# RPiOperantBreakout.net
KiCad netlist of a schematic drawn in EAGLE
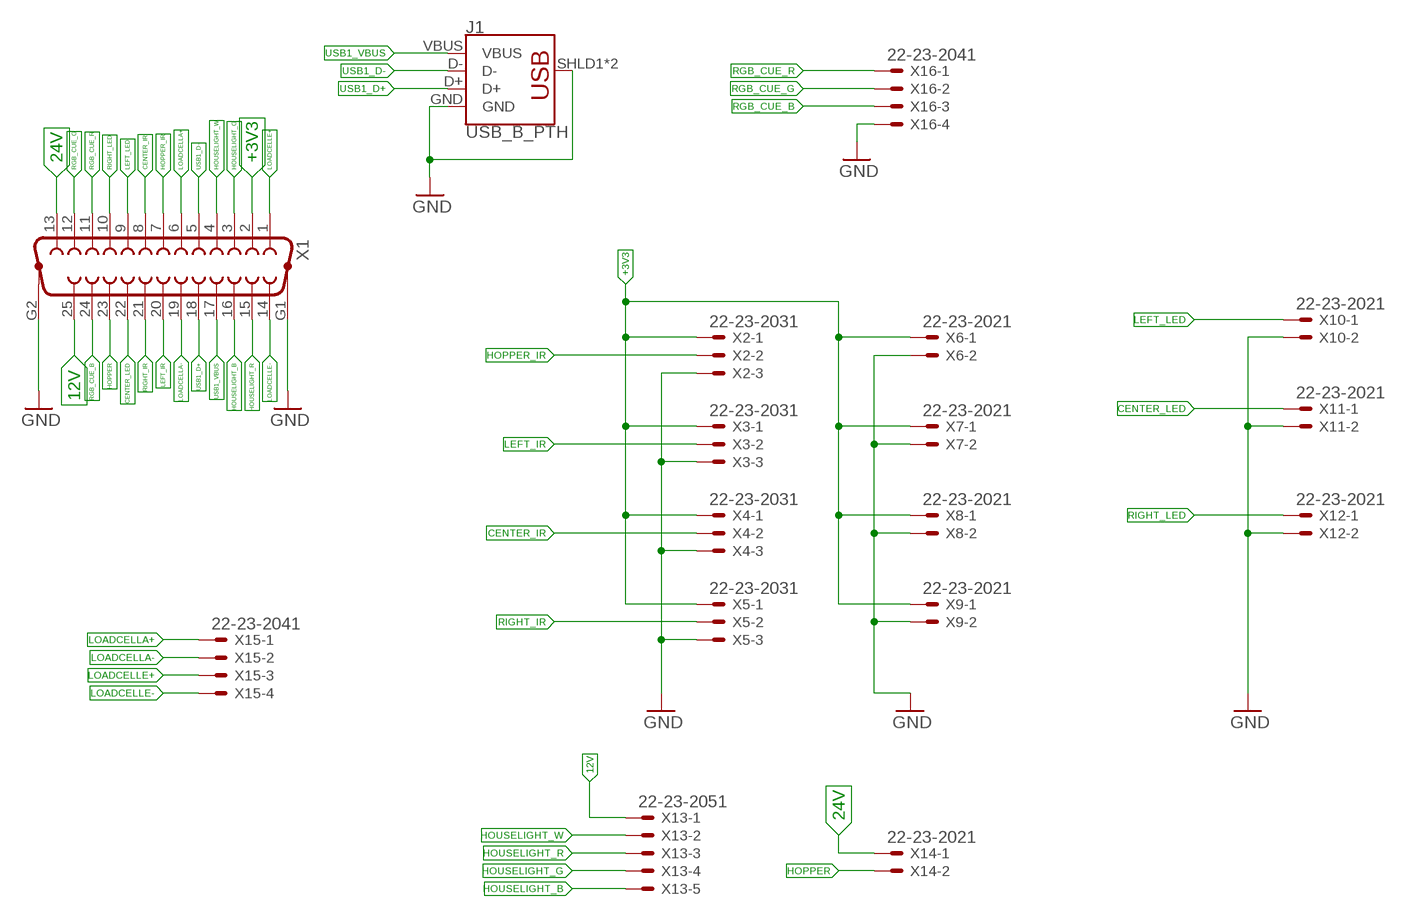
[diagram p0: schematic, sheet 1]

(export (version "E")
  (design (tool "Eeschema 10.0.6"))
  (components
    (comp (ref "J1")
      (value "USB_B_PTH")
      (footprint "eagle-import:USB-B-PTH")
      (libsource (lib "eagle-import") (part "USB_B_PTH"))
    )
    (comp (ref "X1")
      (value "F25HP")
      (footprint "eagle-import:F25HP")
      (libsource (lib "eagle-import") (part "F25HP"))
    )
    (comp (ref "X2")
      (value "22-23-2031")
      (footprint "eagle-import:22-23-2031")
      (fields (field (name "MF") "MOLEX"))
      (libsource (lib "eagle-import") (part "22-23-2031"))
    )
    (comp (ref "X3")
      (value "22-23-2031")
      (footprint "eagle-import:22-23-2031")
      (fields (field (name "MF") "MOLEX"))
      (libsource (lib "eagle-import") (part "22-23-2031"))
    )
    (comp (ref "X4")
      (value "22-23-2031")
      (footprint "eagle-import:22-23-2031")
      (fields (field (name "MF") "MOLEX"))
      (libsource (lib "eagle-import") (part "22-23-2031"))
    )
    (comp (ref "X5")
      (value "22-23-2031")
      (footprint "eagle-import:22-23-2031")
      (fields (field (name "MF") "MOLEX"))
      (libsource (lib "eagle-import") (part "22-23-2031"))
    )
    (comp (ref "X6")
      (value "22-23-2021")
      (footprint "eagle-import:22-23-2021")
      (fields (field (name "MF") "MOLEX"))
      (libsource (lib "eagle-import") (part "22-23-2021"))
    )
    (comp (ref "X7")
      (value "22-23-2021")
      (footprint "eagle-import:22-23-2021")
      (fields (field (name "MF") "MOLEX"))
      (libsource (lib "eagle-import") (part "22-23-2021"))
    )
    (comp (ref "X8")
      (value "22-23-2021")
      (footprint "eagle-import:22-23-2021")
      (fields (field (name "MF") "MOLEX"))
      (libsource (lib "eagle-import") (part "22-23-2021"))
    )
    (comp (ref "X9")
      (value "22-23-2021")
      (footprint "eagle-import:22-23-2021")
      (fields (field (name "MF") "MOLEX"))
      (libsource (lib "eagle-import") (part "22-23-2021"))
    )
    (comp (ref "X10")
      (value "22-23-2021")
      (footprint "eagle-import:22-23-2021")
      (fields (field (name "MF") "MOLEX"))
      (libsource (lib "eagle-import") (part "22-23-2021"))
    )
    (comp (ref "X11")
      (value "22-23-2021")
      (footprint "eagle-import:22-23-2021")
      (fields (field (name "MF") "MOLEX"))
      (libsource (lib "eagle-import") (part "22-23-2021"))
    )
    (comp (ref "X12")
      (value "22-23-2021")
      (footprint "eagle-import:22-23-2021")
      (fields (field (name "MF") "MOLEX"))
      (libsource (lib "eagle-import") (part "22-23-2021"))
    )
    (comp (ref "X13")
      (value "22-23-2051")
      (footprint "eagle-import:22-23-2051")
      (fields (field (name "MF") "MOLEX"))
      (libsource (lib "eagle-import") (part "22-23-2051"))
    )
    (comp (ref "X14")
      (value "22-23-2021")
      (footprint "eagle-import:22-23-2021")
      (fields (field (name "MF") "MOLEX"))
      (libsource (lib "eagle-import") (part "22-23-2021"))
    )
    (comp (ref "X15")
      (value "22-23-2041")
      (footprint "eagle-import:22-23-2041")
      (fields (field (name "MF") "MOLEX"))
      (libsource (lib "eagle-import") (part "22-23-2041"))
    )
    (comp (ref "X16")
      (value "22-23-2041")
      (footprint "eagle-import:22-23-2041")
      (fields (field (name "MF") "MOLEX"))
      (libsource (lib "eagle-import") (part "22-23-2041"))
    )
  )
  (nets
    (net (code "1") (name "+3V3") (class "Default")
      (node (ref "X1") (pin "2") (pinfunction "2_2") (pintype "passive"))
      (node (ref "X2") (pin "1") (pinfunction "S_1") (pintype "passive"))
      (node (ref "X3") (pin "1") (pinfunction "S_1") (pintype "passive"))
      (node (ref "X4") (pin "1") (pinfunction "S_1") (pintype "passive"))
      (node (ref "X5") (pin "1") (pinfunction "S_1") (pintype "passive"))
      (node (ref "X6") (pin "1") (pinfunction "S_1") (pintype "passive"))
      (node (ref "X7") (pin "1") (pinfunction "S_1") (pintype "passive"))
      (node (ref "X8") (pin "1") (pinfunction "S_1") (pintype "passive"))
      (node (ref "X9") (pin "1") (pinfunction "S_1") (pintype "passive"))
    )
    (net (code "2") (name "12V") (class "Default")
      (node (ref "X1") (pin "25") (pinfunction "25_25") (pintype "passive"))
      (node (ref "X13") (pin "1") (pinfunction "S_1") (pintype "passive"))
    )
    (net (code "3") (name "24V") (class "Default")
      (node (ref "X1") (pin "13") (pinfunction "13_13") (pintype "passive"))
      (node (ref "X14") (pin "1") (pinfunction "S_1") (pintype "passive"))
    )
    (net (code "4") (name "CENTER_IR") (class "Default")
      (node (ref "X1") (pin "8") (pinfunction "8_8") (pintype "passive"))
      (node (ref "X4") (pin "2") (pinfunction "S_2") (pintype "passive"))
    )
    (net (code "5") (name "CENTER_LED") (class "Default")
      (node (ref "X1") (pin "22") (pinfunction "22_22") (pintype "passive"))
      (node (ref "X11") (pin "1") (pinfunction "S_1") (pintype "passive"))
    )
    (net (code "6") (name "GND") (class "Default")
      (node (ref "J1") (pin "GND") (pinfunction "GND_GND") (pintype "power_in"))
      (node (ref "J1") (pin "SHLD1") (pinfunction "SHIELD_SHLD1") (pintype "bidirectional"))
      (node (ref "J1") (pin "SHLD2") (pinfunction "SHIELD_SHLD2") (pintype "bidirectional"))
      (node (ref "X1") (pin "G1") (pinfunction "G1_G1") (pintype "passive"))
      (node (ref "X1") (pin "G2") (pinfunction "G2_G2") (pintype "passive"))
      (node (ref "X10") (pin "2") (pinfunction "S_2") (pintype "passive"))
      (node (ref "X11") (pin "2") (pinfunction "S_2") (pintype "passive"))
      (node (ref "X12") (pin "2") (pinfunction "S_2") (pintype "passive"))
      (node (ref "X16") (pin "4") (pinfunction "S_4") (pintype "passive"))
      (node (ref "X2") (pin "3") (pinfunction "S_3") (pintype "passive"))
      (node (ref "X3") (pin "3") (pinfunction "S_3") (pintype "passive"))
      (node (ref "X4") (pin "3") (pinfunction "S_3") (pintype "passive"))
      (node (ref "X5") (pin "3") (pinfunction "S_3") (pintype "passive"))
      (node (ref "X6") (pin "2") (pinfunction "S_2") (pintype "passive"))
      (node (ref "X7") (pin "2") (pinfunction "S_2") (pintype "passive"))
      (node (ref "X8") (pin "2") (pinfunction "S_2") (pintype "passive"))
      (node (ref "X9") (pin "2") (pinfunction "S_2") (pintype "passive"))
    )
    (net (code "7") (name "HOPPER") (class "Default")
      (node (ref "X1") (pin "23") (pinfunction "23_23") (pintype "passive"))
      (node (ref "X14") (pin "2") (pinfunction "S_2") (pintype "passive"))
    )
    (net (code "8") (name "HOPPER_IR") (class "Default")
      (node (ref "X1") (pin "7") (pinfunction "7_7") (pintype "passive"))
      (node (ref "X2") (pin "2") (pinfunction "S_2") (pintype "passive"))
    )
    (net (code "9") (name "HOUSELIGHT_B") (class "Default")
      (node (ref "X1") (pin "16") (pinfunction "16_16") (pintype "passive"))
      (node (ref "X13") (pin "5") (pinfunction "S_5") (pintype "passive"))
    )
    (net (code "10") (name "HOUSELIGHT_G") (class "Default")
      (node (ref "X1") (pin "3") (pinfunction "3_3") (pintype "passive"))
      (node (ref "X13") (pin "4") (pinfunction "S_4") (pintype "passive"))
    )
    (net (code "11") (name "HOUSELIGHT_R") (class "Default")
      (node (ref "X1") (pin "15") (pinfunction "15_15") (pintype "passive"))
      (node (ref "X13") (pin "3") (pinfunction "S_3") (pintype "passive"))
    )
    (net (code "12") (name "HOUSELIGHT_W") (class "Default")
      (node (ref "X1") (pin "4") (pinfunction "4_4") (pintype "passive"))
      (node (ref "X13") (pin "2") (pinfunction "S_2") (pintype "passive"))
    )
    (net (code "13") (name "LEFT_IR") (class "Default")
      (node (ref "X1") (pin "20") (pinfunction "20_20") (pintype "passive"))
      (node (ref "X3") (pin "2") (pinfunction "S_2") (pintype "passive"))
    )
    (net (code "14") (name "LEFT_LED") (class "Default")
      (node (ref "X1") (pin "9") (pinfunction "9_9") (pintype "passive"))
      (node (ref "X10") (pin "1") (pinfunction "S_1") (pintype "passive"))
    )
    (net (code "15") (name "LOADCELLA+") (class "Default")
      (node (ref "X1") (pin "6") (pinfunction "6_6") (pintype "passive"))
      (node (ref "X15") (pin "1") (pinfunction "S_1") (pintype "passive"))
    )
    (net (code "16") (name "LOADCELLA-") (class "Default")
      (node (ref "X1") (pin "19") (pinfunction "19_19") (pintype "passive"))
      (node (ref "X15") (pin "2") (pinfunction "S_2") (pintype "passive"))
    )
    (net (code "17") (name "LOADCELLE+") (class "Default")
      (node (ref "X1") (pin "1") (pinfunction "1_1") (pintype "passive"))
      (node (ref "X15") (pin "3") (pinfunction "S_3") (pintype "passive"))
    )
    (net (code "18") (name "LOADCELLE-") (class "Default")
      (node (ref "X1") (pin "14") (pinfunction "14_14") (pintype "passive"))
      (node (ref "X15") (pin "4") (pinfunction "S_4") (pintype "passive"))
    )
    (net (code "19") (name "RGB_CUE_B") (class "Default")
      (node (ref "X1") (pin "24") (pinfunction "24_24") (pintype "passive"))
      (node (ref "X16") (pin "3") (pinfunction "S_3") (pintype "passive"))
    )
    (net (code "20") (name "RGB_CUE_G") (class "Default")
      (node (ref "X1") (pin "12") (pinfunction "12_12") (pintype "passive"))
      (node (ref "X16") (pin "2") (pinfunction "S_2") (pintype "passive"))
    )
    (net (code "21") (name "RGB_CUE_R") (class "Default")
      (node (ref "X1") (pin "11") (pinfunction "11_11") (pintype "passive"))
      (node (ref "X16") (pin "1") (pinfunction "S_1") (pintype "passive"))
    )
    (net (code "22") (name "RIGHT_IR") (class "Default")
      (node (ref "X1") (pin "21") (pinfunction "21_21") (pintype "passive"))
      (node (ref "X5") (pin "2") (pinfunction "S_2") (pintype "passive"))
    )
    (net (code "23") (name "RIGHT_LED") (class "Default")
      (node (ref "X1") (pin "10") (pinfunction "10_10") (pintype "passive"))
      (node (ref "X12") (pin "1") (pinfunction "S_1") (pintype "passive"))
    )
    (net (code "24") (name "USB1_D+") (class "Default")
      (node (ref "J1") (pin "D+") (pinfunction "D+_D+") (pintype "bidirectional"))
      (node (ref "X1") (pin "18") (pinfunction "18_18") (pintype "passive"))
    )
    (net (code "25") (name "USB1_D-") (class "Default")
      (node (ref "J1") (pin "D-") (pinfunction "D-_D-") (pintype "bidirectional"))
      (node (ref "X1") (pin "5") (pinfunction "5_5") (pintype "passive"))
    )
    (net (code "26") (name "USB1_VBUS") (class "Default")
      (node (ref "J1") (pin "VBUS") (pinfunction "VBUS_VBUS") (pintype "power_in"))
      (node (ref "X1") (pin "17") (pinfunction "17_17") (pintype "passive"))
    )
  )
)
